# CCM0004.net
KiCad netlist of a schematic drawn in EAGLE
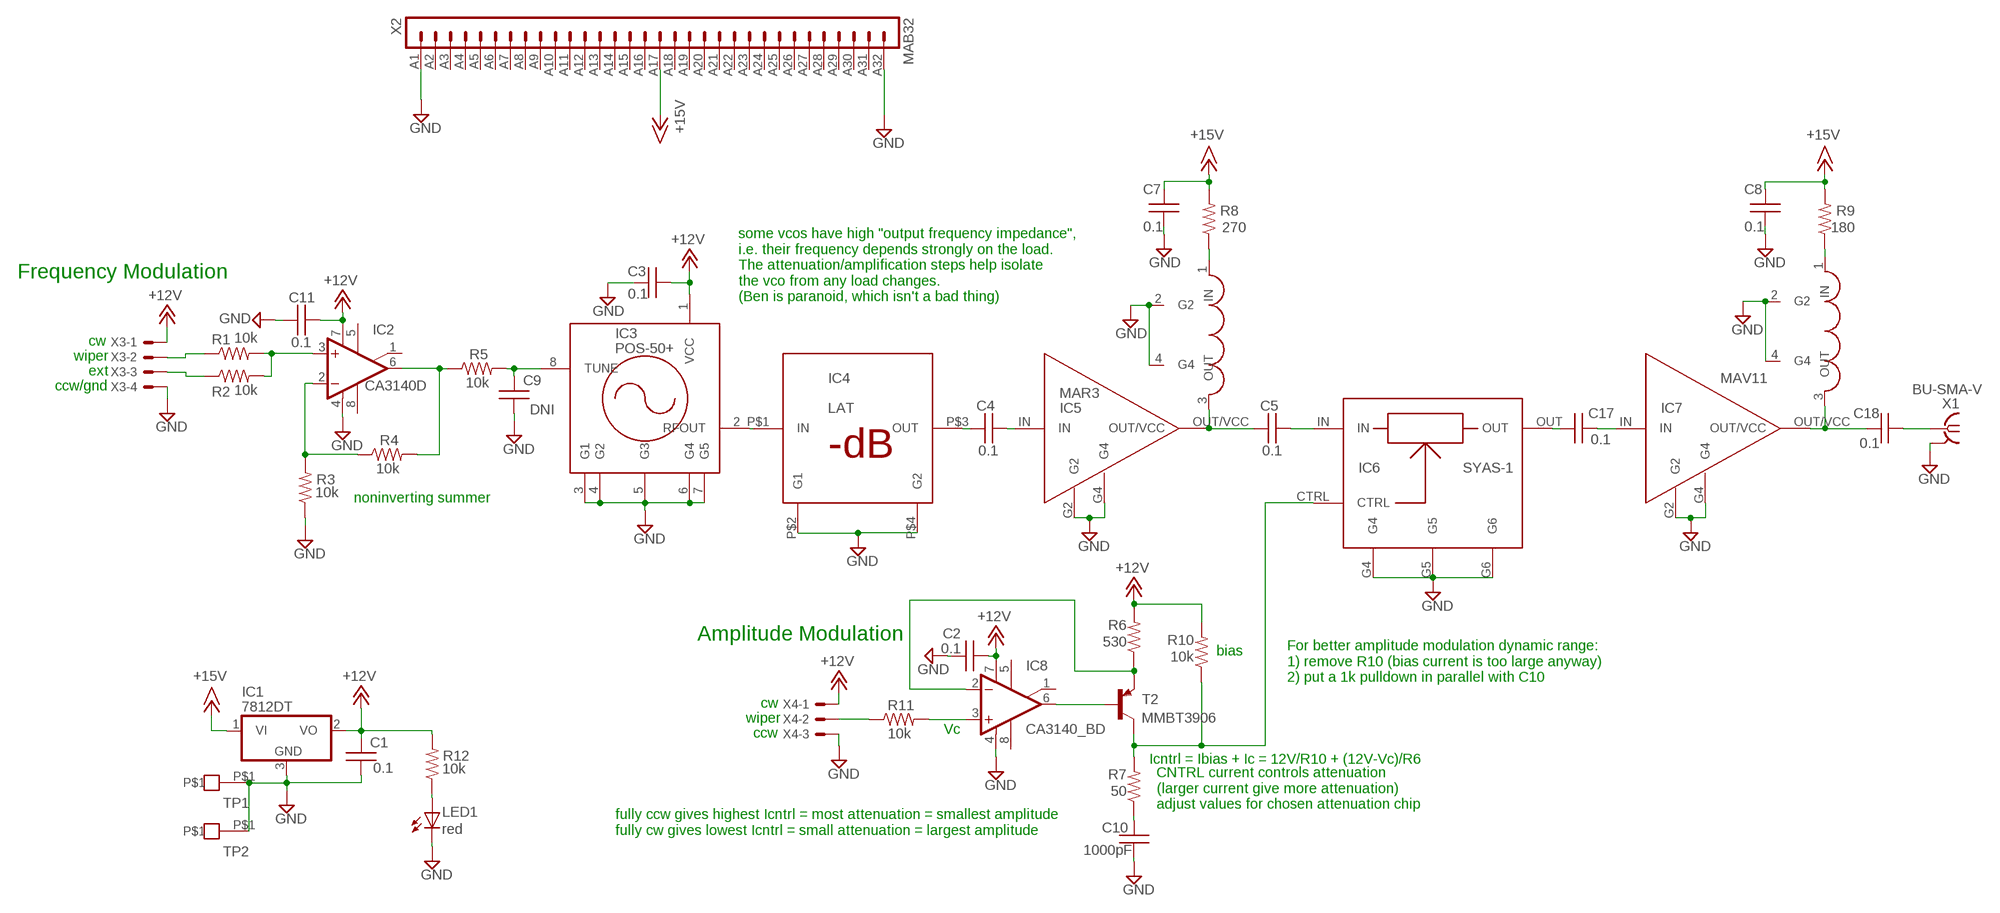
[diagram p0: schematic, sheet 1]

(export (version "E")
  (design (tool "Eeschema 10.0.6"))
  (components
    (comp (ref "C1")
      (value "0.1")
      (footprint "eagle-import:0603")
      (libsource (lib "eagle-import") (part "CAPACITOR0603"))
    )
    (comp (ref "C2")
      (value "0.1")
      (footprint "eagle-import:0603")
      (libsource (lib "eagle-import") (part "CAPACITOR0603"))
    )
    (comp (ref "C3")
      (value "0.1")
      (footprint "eagle-import:0603")
      (libsource (lib "eagle-import") (part "CAPACITOR0603"))
    )
    (comp (ref "C4")
      (value "0.1")
      (footprint "eagle-import:2010")
      (libsource (lib "eagle-import") (part "CAPACITOR2010"))
    )
    (comp (ref "C5")
      (value "0.1")
      (footprint "eagle-import:2010")
      (libsource (lib "eagle-import") (part "CAPACITOR2010"))
    )
    (comp (ref "C7")
      (value "0.1")
      (footprint "eagle-import:0603")
      (libsource (lib "eagle-import") (part "CAPACITOR0603"))
    )
    (comp (ref "C8")
      (value "0.1")
      (footprint "eagle-import:0603")
      (libsource (lib "eagle-import") (part "CAPACITOR0603"))
    )
    (comp (ref "C9")
      (value "DNI")
      (footprint "eagle-import:0603")
      (libsource (lib "eagle-import") (part "CAPACITOR0603"))
    )
    (comp (ref "C10")
      (value "1000pF")
      (footprint "eagle-import:2010")
      (libsource (lib "eagle-import") (part "CAPACITOR2010"))
    )
    (comp (ref "C11")
      (value "0.1")
      (footprint "eagle-import:0603")
      (libsource (lib "eagle-import") (part "CAPACITOR0603"))
    )
    (comp (ref "C17")
      (value "0.1")
      (footprint "eagle-import:2010")
      (libsource (lib "eagle-import") (part "CAPACITOR2010"))
    )
    (comp (ref "C18")
      (value "0.1")
      (footprint "eagle-import:2010")
      (libsource (lib "eagle-import") (part "CAPACITOR2010"))
    )
    (comp (ref "IC1")
      (value "7812DT")
      (footprint "eagle-import:TO252")
      (libsource (lib "eagle-import") (part "78DT12"))
    )
    (comp (ref "IC2")
      (value "CA3140D")
      (footprint "eagle-import:SO08")
      (libsource (lib "eagle-import") (part "CA3140D"))
    )
    (comp (ref "IC3")
      (value "POS-50+")
      (footprint "eagle-import:A01")
      (libsource (lib "eagle-import") (part "POS"))
    )
    (comp (ref "IC4")
      (value "LAT")
      (footprint "eagle-import:MMM168")
      (libsource (lib "eagle-import") (part "LAT"))
    )
    (comp (ref "IC5")
      (value "MAR3")
      (footprint "eagle-import:MAR")
      (libsource (lib "eagle-import") (part "MAR3"))
    )
    (comp (ref "IC6")
      (value "SYAS-1")
      (footprint "eagle-import:TTT166")
      (libsource (lib "eagle-import") (part "SYAS-1"))
    )
    (comp (ref "IC7")
      (value "MAV11")
      (footprint "eagle-import:MAR")
      (libsource (lib "eagle-import") (part "MAV11"))
    )
    (comp (ref "IC8")
      (value "CA3140_BD")
      (footprint "eagle-import:SO08")
      (libsource (lib "eagle-import") (part "CA3140_BD"))
    )
    (comp (ref "L1")
      (value "TCCH-80")
      (footprint "eagle-import:PL-147")
      (libsource (lib "eagle-import") (part "TCCH-80"))
    )
    (comp (ref "L2")
      (value "TCCH-80")
      (footprint "eagle-import:PL-147")
      (libsource (lib "eagle-import") (part "TCCH-80"))
    )
    (comp (ref "LED1")
      (value "red")
      (footprint "eagle-import:CHIPLED_0603")
      (libsource (lib "eagle-import") (part "LEDCHIPLED_0603"))
    )
    (comp (ref "R1")
      (value "10k")
      (footprint "eagle-import:0603")
      (libsource (lib "eagle-import") (part "RESISTOR0603"))
    )
    (comp (ref "R2")
      (value "10k")
      (footprint "eagle-import:0603")
      (libsource (lib "eagle-import") (part "RESISTOR0603"))
    )
    (comp (ref "R3")
      (value "10k")
      (footprint "eagle-import:0603")
      (libsource (lib "eagle-import") (part "RESISTOR0603"))
    )
    (comp (ref "R4")
      (value "10k")
      (footprint "eagle-import:0603")
      (libsource (lib "eagle-import") (part "RESISTOR0603"))
    )
    (comp (ref "R5")
      (value "10k")
      (footprint "eagle-import:0603")
      (libsource (lib "eagle-import") (part "RESISTOR0603"))
    )
    (comp (ref "R6")
      (value "530")
      (footprint "eagle-import:2010")
      (libsource (lib "eagle-import") (part "RESISTOR2010"))
    )
    (comp (ref "R7")
      (value "50")
      (footprint "eagle-import:2010")
      (libsource (lib "eagle-import") (part "RESISTOR2010"))
    )
    (comp (ref "R8")
      (value "270")
      (footprint "eagle-import:2010")
      (libsource (lib "eagle-import") (part "RESISTOR2010"))
    )
    (comp (ref "R9")
      (value "180")
      (footprint "eagle-import:2010")
      (libsource (lib "eagle-import") (part "RESISTOR2010"))
    )
    (comp (ref "R10")
      (value "10k")
      (footprint "eagle-import:2010")
      (libsource (lib "eagle-import") (part "RESISTOR2010"))
    )
    (comp (ref "R11")
      (value "10k")
      (footprint "eagle-import:0603")
      (libsource (lib "eagle-import") (part "RESISTOR0603"))
    )
    (comp (ref "R12")
      (value "10k")
      (footprint "eagle-import:0603")
      (libsource (lib "eagle-import") (part "RESISTOR0603"))
    )
    (comp (ref "T2")
      (value "MMBT3906")
      (footprint "eagle-import:SOT23-BEC")
      (libsource (lib "eagle-import") (part "MMBT3906SMDLT1"))
    )
    (comp (ref "TP1")
      (value "TESTPOINT")
      (footprint "eagle-import:TESTPOINT")
      (libsource (lib "eagle-import") (part "TESTPOINT"))
    )
    (comp (ref "TP2")
      (value "TESTPOINT")
      (footprint "eagle-import:TESTPOINT")
      (libsource (lib "eagle-import") (part "TESTPOINT"))
    )
    (comp (ref "X1")
      (value "BU-SMA-V")
      (footprint "eagle-import:BU-SMA-V")
      (libsource (lib "eagle-import") (part "BU-SMA-V"))
    )
    (comp (ref "X2")
      (value "MAB32")
      (footprint "eagle-import:MAB32")
      (libsource (lib "eagle-import") (part "MAB32"))
    )
    (comp (ref "X3")
      (value "22-23-2041")
      (footprint "eagle-import:22-23-2041")
      (fields (field (name "MF") "MOLEX"))
      (libsource (lib "eagle-import") (part "22-23-2041"))
    )
    (comp (ref "X4")
      (value "22-23-2031")
      (footprint "eagle-import:22-23-2031")
      (fields (field (name "MF") "MOLEX"))
      (libsource (lib "eagle-import") (part "22-23-2031"))
    )
  )
  (nets
    (net (code "1") (name "+12V") (class "Default")
      (node (ref "C1") (pin "1") (pinfunction "1_1") (pintype "passive"))
      (node (ref "C11") (pin "2") (pinfunction "2_2") (pintype "passive"))
      (node (ref "C2") (pin "2") (pinfunction "2_2") (pintype "passive"))
      (node (ref "C3") (pin "1") (pinfunction "1_1") (pintype "passive"))
      (node (ref "IC1") (pin "2") (pinfunction "VO_2") (pintype "passive"))
      (node (ref "IC2") (pin "7") (pinfunction "V+_7") (pintype "power_in"))
      (node (ref "IC3") (pin "1") (pinfunction "VCC_1") (pintype "input"))
      (node (ref "IC8") (pin "7") (pinfunction "V+_7") (pintype "power_in"))
      (node (ref "R10") (pin "2") (pinfunction "2_2") (pintype "passive"))
      (node (ref "R12") (pin "2") (pinfunction "2_2") (pintype "passive"))
      (node (ref "R6") (pin "2") (pinfunction "2_2") (pintype "passive"))
      (node (ref "X3") (pin "1") (pinfunction "S_1") (pintype "passive"))
      (node (ref "X4") (pin "1") (pinfunction "S_1") (pintype "passive"))
    )
    (net (code "2") (name "+15V") (class "Default")
      (node (ref "C7") (pin "1") (pinfunction "1_1") (pintype "passive"))
      (node (ref "C8") (pin "1") (pinfunction "1_1") (pintype "passive"))
      (node (ref "IC1") (pin "1") (pinfunction "VI_1") (pintype "input"))
      (node (ref "R8") (pin "2") (pinfunction "2_2") (pintype "passive"))
      (node (ref "R9") (pin "2") (pinfunction "2_2") (pintype "passive"))
      (node (ref "X2") (pin "A17") (pinfunction "17_A17") (pintype "passive"))
    )
    (net (code "3") (name "GND") (class "Default")
      (node (ref "C1") (pin "2") (pinfunction "2_2") (pintype "passive"))
      (node (ref "C10") (pin "1") (pinfunction "1_1") (pintype "passive"))
      (node (ref "C11") (pin "1") (pinfunction "1_1") (pintype "passive"))
      (node (ref "C2") (pin "1") (pinfunction "1_1") (pintype "passive"))
      (node (ref "C3") (pin "2") (pinfunction "2_2") (pintype "passive"))
      (node (ref "C7") (pin "2") (pinfunction "2_2") (pintype "passive"))
      (node (ref "C8") (pin "2") (pinfunction "2_2") (pintype "passive"))
      (node (ref "C9") (pin "2") (pinfunction "2_2") (pintype "passive"))
      (node (ref "IC1") (pin "3") (pinfunction "GND_3") (pintype "passive"))
      (node (ref "IC2") (pin "4") (pinfunction "V-_4") (pintype "power_in"))
      (node (ref "IC3") (pin "3") (pinfunction "G1_3") (pintype "power_in"))
      (node (ref "IC3") (pin "4") (pinfunction "G2_4") (pintype "power_in"))
      (node (ref "IC3") (pin "5") (pinfunction "G3_5") (pintype "power_in"))
      (node (ref "IC3") (pin "6") (pinfunction "G4_6") (pintype "power_in"))
      (node (ref "IC3") (pin "7") (pinfunction "G5_7") (pintype "power_in"))
      (node (ref "IC4") (pin "P$2") (pinfunction "G1_P$2") (pintype "power_in"))
      (node (ref "IC4") (pin "P$4") (pinfunction "G2_P$4") (pintype "power_in"))
      (node (ref "IC5") (pin "G2") (pinfunction "G2_G2") (pintype "power_in"))
      (node (ref "IC5") (pin "G4") (pinfunction "G4_G4") (pintype "power_in"))
      (node (ref "IC6") (pin "G4") (pinfunction "G4_G4") (pintype "power_in"))
      (node (ref "IC6") (pin "G5") (pinfunction "G5_G5") (pintype "power_in"))
      (node (ref "IC6") (pin "G6") (pinfunction "G6_G6") (pintype "power_in"))
      (node (ref "IC7") (pin "G2") (pinfunction "G2_G2") (pintype "power_in"))
      (node (ref "IC7") (pin "G4") (pinfunction "G4_G4") (pintype "power_in"))
      (node (ref "IC8") (pin "4") (pinfunction "V-_4") (pintype "power_in"))
      (node (ref "L1") (pin "2") (pinfunction "G2_2") (pintype "power_in"))
      (node (ref "L1") (pin "4") (pinfunction "G4_4") (pintype "power_in"))
      (node (ref "L2") (pin "2") (pinfunction "G2_2") (pintype "power_in"))
      (node (ref "L2") (pin "4") (pinfunction "G4_4") (pintype "power_in"))
      (node (ref "LED1") (pin "C") (pinfunction "C_C") (pintype "passive"))
      (node (ref "R3") (pin "1") (pinfunction "1_1") (pintype "passive"))
      (node (ref "TP1") (pin "P$1") (pinfunction "P$1_P$1") (pintype "bidirectional"))
      (node (ref "TP2") (pin "P$1") (pinfunction "P$1_P$1") (pintype "bidirectional"))
      (node (ref "X1") (pin "2") (pinfunction "GND_2") (pintype "power_in"))
      (node (ref "X2") (pin "A1") (pinfunction "1_A1") (pintype "passive"))
      (node (ref "X2") (pin "A32") (pinfunction "32_A32") (pintype "passive"))
      (node (ref "X3") (pin "4") (pinfunction "S_4") (pintype "passive"))
      (node (ref "X4") (pin "3") (pinfunction "S_3") (pintype "passive"))
    )
    (net (code "4") (name "Net-(C4-Pad2)") (class "Default")
      (node (ref "C4") (pin "2") (pinfunction "2_2") (pintype "passive"))
      (node (ref "IC5") (pin "IN") (pinfunction "IN_IN") (pintype "input"))
    )
    (net (code "5") (name "Net-(C5-Pad2)") (class "Default")
      (node (ref "C5") (pin "2") (pinfunction "2_2") (pintype "passive"))
      (node (ref "IC6") (pin "IN") (pinfunction "IN_IN") (pintype "input"))
    )
    (net (code "6") (name "Net-(C10-Pad2)") (class "Default")
      (node (ref "C10") (pin "2") (pinfunction "2_2") (pintype "passive"))
      (node (ref "R7") (pin "1") (pinfunction "1_1") (pintype "passive"))
    )
    (net (code "7") (name "Net-(C17-Pad1)") (class "Default")
      (node (ref "C17") (pin "1") (pinfunction "1_1") (pintype "passive"))
      (node (ref "IC6") (pin "OUT") (pinfunction "OUT_OUT") (pintype "output"))
    )
    (net (code "8") (name "Net-(C17-Pad2)") (class "Default")
      (node (ref "C17") (pin "2") (pinfunction "2_2") (pintype "passive"))
      (node (ref "IC7") (pin "IN") (pinfunction "IN_IN") (pintype "input"))
    )
    (net (code "9") (name "Net-(C18-Pad2)") (class "Default")
      (node (ref "C18") (pin "2") (pinfunction "2_2") (pintype "passive"))
      (node (ref "X1") (pin "1") (pinfunction "1_1") (pintype "passive"))
    )
    (net (code "10") (name "Net-(IC2-+IN)") (class "Default")
      (node (ref "IC2") (pin "3") (pinfunction "+IN_3") (pintype "input"))
      (node (ref "R1") (pin "2") (pinfunction "2_2") (pintype "passive"))
      (node (ref "R2") (pin "2") (pinfunction "2_2") (pintype "passive"))
    )
    (net (code "11") (name "Net-(IC2--IN)") (class "Default")
      (node (ref "IC2") (pin "2") (pinfunction "-IN_2") (pintype "input"))
      (node (ref "R3") (pin "2") (pinfunction "2_2") (pintype "passive"))
      (node (ref "R4") (pin "1") (pinfunction "1_1") (pintype "passive"))
    )
    (net (code "12") (name "Net-(IC2-OUT)") (class "Default")
      (node (ref "IC2") (pin "6") (pinfunction "OUT_6") (pintype "output"))
      (node (ref "R4") (pin "2") (pinfunction "2_2") (pintype "passive"))
      (node (ref "R5") (pin "1") (pinfunction "1_1") (pintype "passive"))
    )
    (net (code "13") (name "Net-(IC3-RFOUT)") (class "Default")
      (node (ref "IC3") (pin "2") (pinfunction "RFOUT_2") (pintype "output"))
      (node (ref "IC4") (pin "P$1") (pinfunction "IN_P$1") (pintype "input"))
    )
    (net (code "14") (name "Net-(IC3-TUNE)") (class "Default")
      (node (ref "C9") (pin "1") (pinfunction "1_1") (pintype "passive"))
      (node (ref "IC3") (pin "8") (pinfunction "TUNE_8") (pintype "input"))
      (node (ref "R5") (pin "2") (pinfunction "2_2") (pintype "passive"))
    )
    (net (code "15") (name "Net-(IC4-OUT)") (class "Default")
      (node (ref "C4") (pin "1") (pinfunction "1_1") (pintype "passive"))
      (node (ref "IC4") (pin "P$3") (pinfunction "OUT_P$3") (pintype "output"))
    )
    (net (code "16") (name "Net-(IC6-PadCTRL)") (class "Default")
      (node (ref "IC6") (pin "CTRL") (pinfunction "CTRL_CTRL") (pintype "input"))
      (node (ref "R10") (pin "1") (pinfunction "1_1") (pintype "passive"))
      (node (ref "R7") (pin "2") (pinfunction "2_2") (pintype "passive"))
      (node (ref "T2") (pin "C") (pinfunction "C_C") (pintype "passive"))
    )
    (net (code "17") (name "Net-(IC8-+IN)") (class "Default")
      (node (ref "IC8") (pin "3") (pinfunction "+IN_3") (pintype "input"))
      (node (ref "R11") (pin "2") (pinfunction "2_2") (pintype "passive"))
    )
    (net (code "18") (name "Net-(IC8--IN)") (class "Default")
      (node (ref "IC8") (pin "2") (pinfunction "-IN_2") (pintype "input"))
      (node (ref "R6") (pin "1") (pinfunction "1_1") (pintype "passive"))
      (node (ref "T2") (pin "E") (pinfunction "E_E") (pintype "passive"))
    )
    (net (code "19") (name "Net-(IC8-OUT)") (class "Default")
      (node (ref "IC8") (pin "6") (pinfunction "OUT_6") (pintype "output"))
      (node (ref "T2") (pin "B") (pinfunction "B_B") (pintype "passive"))
    )
    (net (code "20") (name "Net-(L1-IN)") (class "Default")
      (node (ref "L1") (pin "1") (pinfunction "IN_1") (pintype "input"))
      (node (ref "R8") (pin "1") (pinfunction "1_1") (pintype "passive"))
    )
    (net (code "21") (name "Net-(L1-OUT)") (class "Default")
      (node (ref "C5") (pin "1") (pinfunction "1_1") (pintype "passive"))
      (node (ref "IC5") (pin "OUT/VCC") (pinfunction "OUT/VCC_OUT/VCC") (pintype "bidirectional"))
      (node (ref "L1") (pin "3") (pinfunction "OUT_3") (pintype "output"))
    )
    (net (code "22") (name "Net-(L2-IN)") (class "Default")
      (node (ref "L2") (pin "1") (pinfunction "IN_1") (pintype "input"))
      (node (ref "R9") (pin "1") (pinfunction "1_1") (pintype "passive"))
    )
    (net (code "23") (name "Net-(L2-OUT)") (class "Default")
      (node (ref "C18") (pin "1") (pinfunction "1_1") (pintype "passive"))
      (node (ref "IC7") (pin "OUT/VCC") (pinfunction "OUT/VCC_OUT/VCC") (pintype "bidirectional"))
      (node (ref "L2") (pin "3") (pinfunction "OUT_3") (pintype "output"))
    )
    (net (code "24") (name "Net-(LED1-PadA)") (class "Default")
      (node (ref "LED1") (pin "A") (pinfunction "A_A") (pintype "passive"))
      (node (ref "R12") (pin "1") (pinfunction "1_1") (pintype "passive"))
    )
    (net (code "25") (name "Net-(X3B-S)") (class "Default")
      (node (ref "R1") (pin "1") (pinfunction "1_1") (pintype "passive"))
      (node (ref "X3") (pin "2") (pinfunction "S_2") (pintype "passive"))
    )
    (net (code "26") (name "Net-(X3C-S)") (class "Default")
      (node (ref "R2") (pin "1") (pinfunction "1_1") (pintype "passive"))
      (node (ref "X3") (pin "3") (pinfunction "S_3") (pintype "passive"))
    )
    (net (code "27") (name "Net-(X4B-S)") (class "Default")
      (node (ref "R11") (pin "1") (pinfunction "1_1") (pintype "passive"))
      (node (ref "X4") (pin "2") (pinfunction "S_2") (pintype "passive"))
    )
    (net (code "28") (name "unconnected-(IC2-CMP-Pad8)") (class "Default")
      (node (ref "IC2") (pin "8") (pinfunction "CMP_8") (pintype "passive"))
    )
    (net (code "29") (name "unconnected-(IC2-ON-Pad5)") (class "Default")
      (node (ref "IC2") (pin "5") (pinfunction "ON_5") (pintype "passive"))
    )
    (net (code "30") (name "unconnected-(IC2-ON{slash}CMP-Pad1)") (class "Default")
      (node (ref "IC2") (pin "1") (pinfunction "ON/CMP_1") (pintype "passive"))
    )
    (net (code "31") (name "unconnected-(IC8-CMP-Pad8)") (class "Default")
      (node (ref "IC8") (pin "8") (pinfunction "CMP_8") (pintype "passive"))
    )
    (net (code "32") (name "unconnected-(IC8-ON-Pad5)") (class "Default")
      (node (ref "IC8") (pin "5") (pinfunction "ON_5") (pintype "passive"))
    )
    (net (code "33") (name "unconnected-(IC8-ON{slash}CMP-Pad1)") (class "Default")
      (node (ref "IC8") (pin "1") (pinfunction "ON/CMP_1") (pintype "passive"))
    )
    (net (code "34") (name "unconnected-(X2-2-PadA2)") (class "Default")
      (node (ref "X2") (pin "A2") (pinfunction "2_A2") (pintype "passive"))
    )
    (net (code "35") (name "unconnected-(X2-3-PadA3)") (class "Default")
      (node (ref "X2") (pin "A3") (pinfunction "3_A3") (pintype "passive"))
    )
    (net (code "36") (name "unconnected-(X2-4-PadA4)") (class "Default")
      (node (ref "X2") (pin "A4") (pinfunction "4_A4") (pintype "passive"))
    )
    (net (code "37") (name "unconnected-(X2-5-PadA5)") (class "Default")
      (node (ref "X2") (pin "A5") (pinfunction "5_A5") (pintype "passive"))
    )
    (net (code "38") (name "unconnected-(X2-6-PadA6)") (class "Default")
      (node (ref "X2") (pin "A6") (pinfunction "6_A6") (pintype "passive"))
    )
    (net (code "39") (name "unconnected-(X2-7-PadA7)") (class "Default")
      (node (ref "X2") (pin "A7") (pinfunction "7_A7") (pintype "passive"))
    )
    (net (code "40") (name "unconnected-(X2-8-PadA8)") (class "Default")
      (node (ref "X2") (pin "A8") (pinfunction "8_A8") (pintype "passive"))
    )
    (net (code "41") (name "unconnected-(X2-9-PadA9)") (class "Default")
      (node (ref "X2") (pin "A9") (pinfunction "9_A9") (pintype "passive"))
    )
    (net (code "42") (name "unconnected-(X2-10-PadA10)") (class "Default")
      (node (ref "X2") (pin "A10") (pinfunction "10_A10") (pintype "passive"))
    )
    (net (code "43") (name "unconnected-(X2-11-PadA11)") (class "Default")
      (node (ref "X2") (pin "A11") (pinfunction "11_A11") (pintype "passive"))
    )
    (net (code "44") (name "unconnected-(X2-12-PadA12)") (class "Default")
      (node (ref "X2") (pin "A12") (pinfunction "12_A12") (pintype "passive"))
    )
    (net (code "45") (name "unconnected-(X2-13-PadA13)") (class "Default")
      (node (ref "X2") (pin "A13") (pinfunction "13_A13") (pintype "passive"))
    )
    (net (code "46") (name "unconnected-(X2-14-PadA14)") (class "Default")
      (node (ref "X2") (pin "A14") (pinfunction "14_A14") (pintype "passive"))
    )
    (net (code "47") (name "unconnected-(X2-15-PadA15)") (class "Default")
      (node (ref "X2") (pin "A15") (pinfunction "15_A15") (pintype "passive"))
    )
    (net (code "48") (name "unconnected-(X2-16-PadA16)") (class "Default")
      (node (ref "X2") (pin "A16") (pinfunction "16_A16") (pintype "passive"))
    )
    (net (code "49") (name "unconnected-(X2-18-PadA18)") (class "Default")
      (node (ref "X2") (pin "A18") (pinfunction "18_A18") (pintype "passive"))
    )
    (net (code "50") (name "unconnected-(X2-19-PadA19)") (class "Default")
      (node (ref "X2") (pin "A19") (pinfunction "19_A19") (pintype "passive"))
    )
    (net (code "51") (name "unconnected-(X2-20-PadA20)") (class "Default")
      (node (ref "X2") (pin "A20") (pinfunction "20_A20") (pintype "passive"))
    )
    (net (code "52") (name "unconnected-(X2-21-PadA21)") (class "Default")
      (node (ref "X2") (pin "A21") (pinfunction "21_A21") (pintype "passive"))
    )
    (net (code "53") (name "unconnected-(X2-22-PadA22)") (class "Default")
      (node (ref "X2") (pin "A22") (pinfunction "22_A22") (pintype "passive"))
    )
    (net (code "54") (name "unconnected-(X2-23-PadA23)") (class "Default")
      (node (ref "X2") (pin "A23") (pinfunction "23_A23") (pintype "passive"))
    )
    (net (code "55") (name "unconnected-(X2-24-PadA24)") (class "Default")
      (node (ref "X2") (pin "A24") (pinfunction "24_A24") (pintype "passive"))
    )
    (net (code "56") (name "unconnected-(X2-25-PadA25)") (class "Default")
      (node (ref "X2") (pin "A25") (pinfunction "25_A25") (pintype "passive"))
    )
    (net (code "57") (name "unconnected-(X2-26-PadA26)") (class "Default")
      (node (ref "X2") (pin "A26") (pinfunction "26_A26") (pintype "passive"))
    )
    (net (code "58") (name "unconnected-(X2-27-PadA27)") (class "Default")
      (node (ref "X2") (pin "A27") (pinfunction "27_A27") (pintype "passive"))
    )
    (net (code "59") (name "unconnected-(X2-28-PadA28)") (class "Default")
      (node (ref "X2") (pin "A28") (pinfunction "28_A28") (pintype "passive"))
    )
    (net (code "60") (name "unconnected-(X2-29-PadA29)") (class "Default")
      (node (ref "X2") (pin "A29") (pinfunction "29_A29") (pintype "passive"))
    )
    (net (code "61") (name "unconnected-(X2-30-PadA30)") (class "Default")
      (node (ref "X2") (pin "A30") (pinfunction "30_A30") (pintype "passive"))
    )
    (net (code "62") (name "unconnected-(X2-31-PadA31)") (class "Default")
      (node (ref "X2") (pin "A31") (pinfunction "31_A31") (pintype "passive"))
    )
  )
)
